# 2_BLE-T2_matrix.net
KiCad netlist of a schematic drawn in Altium Designer
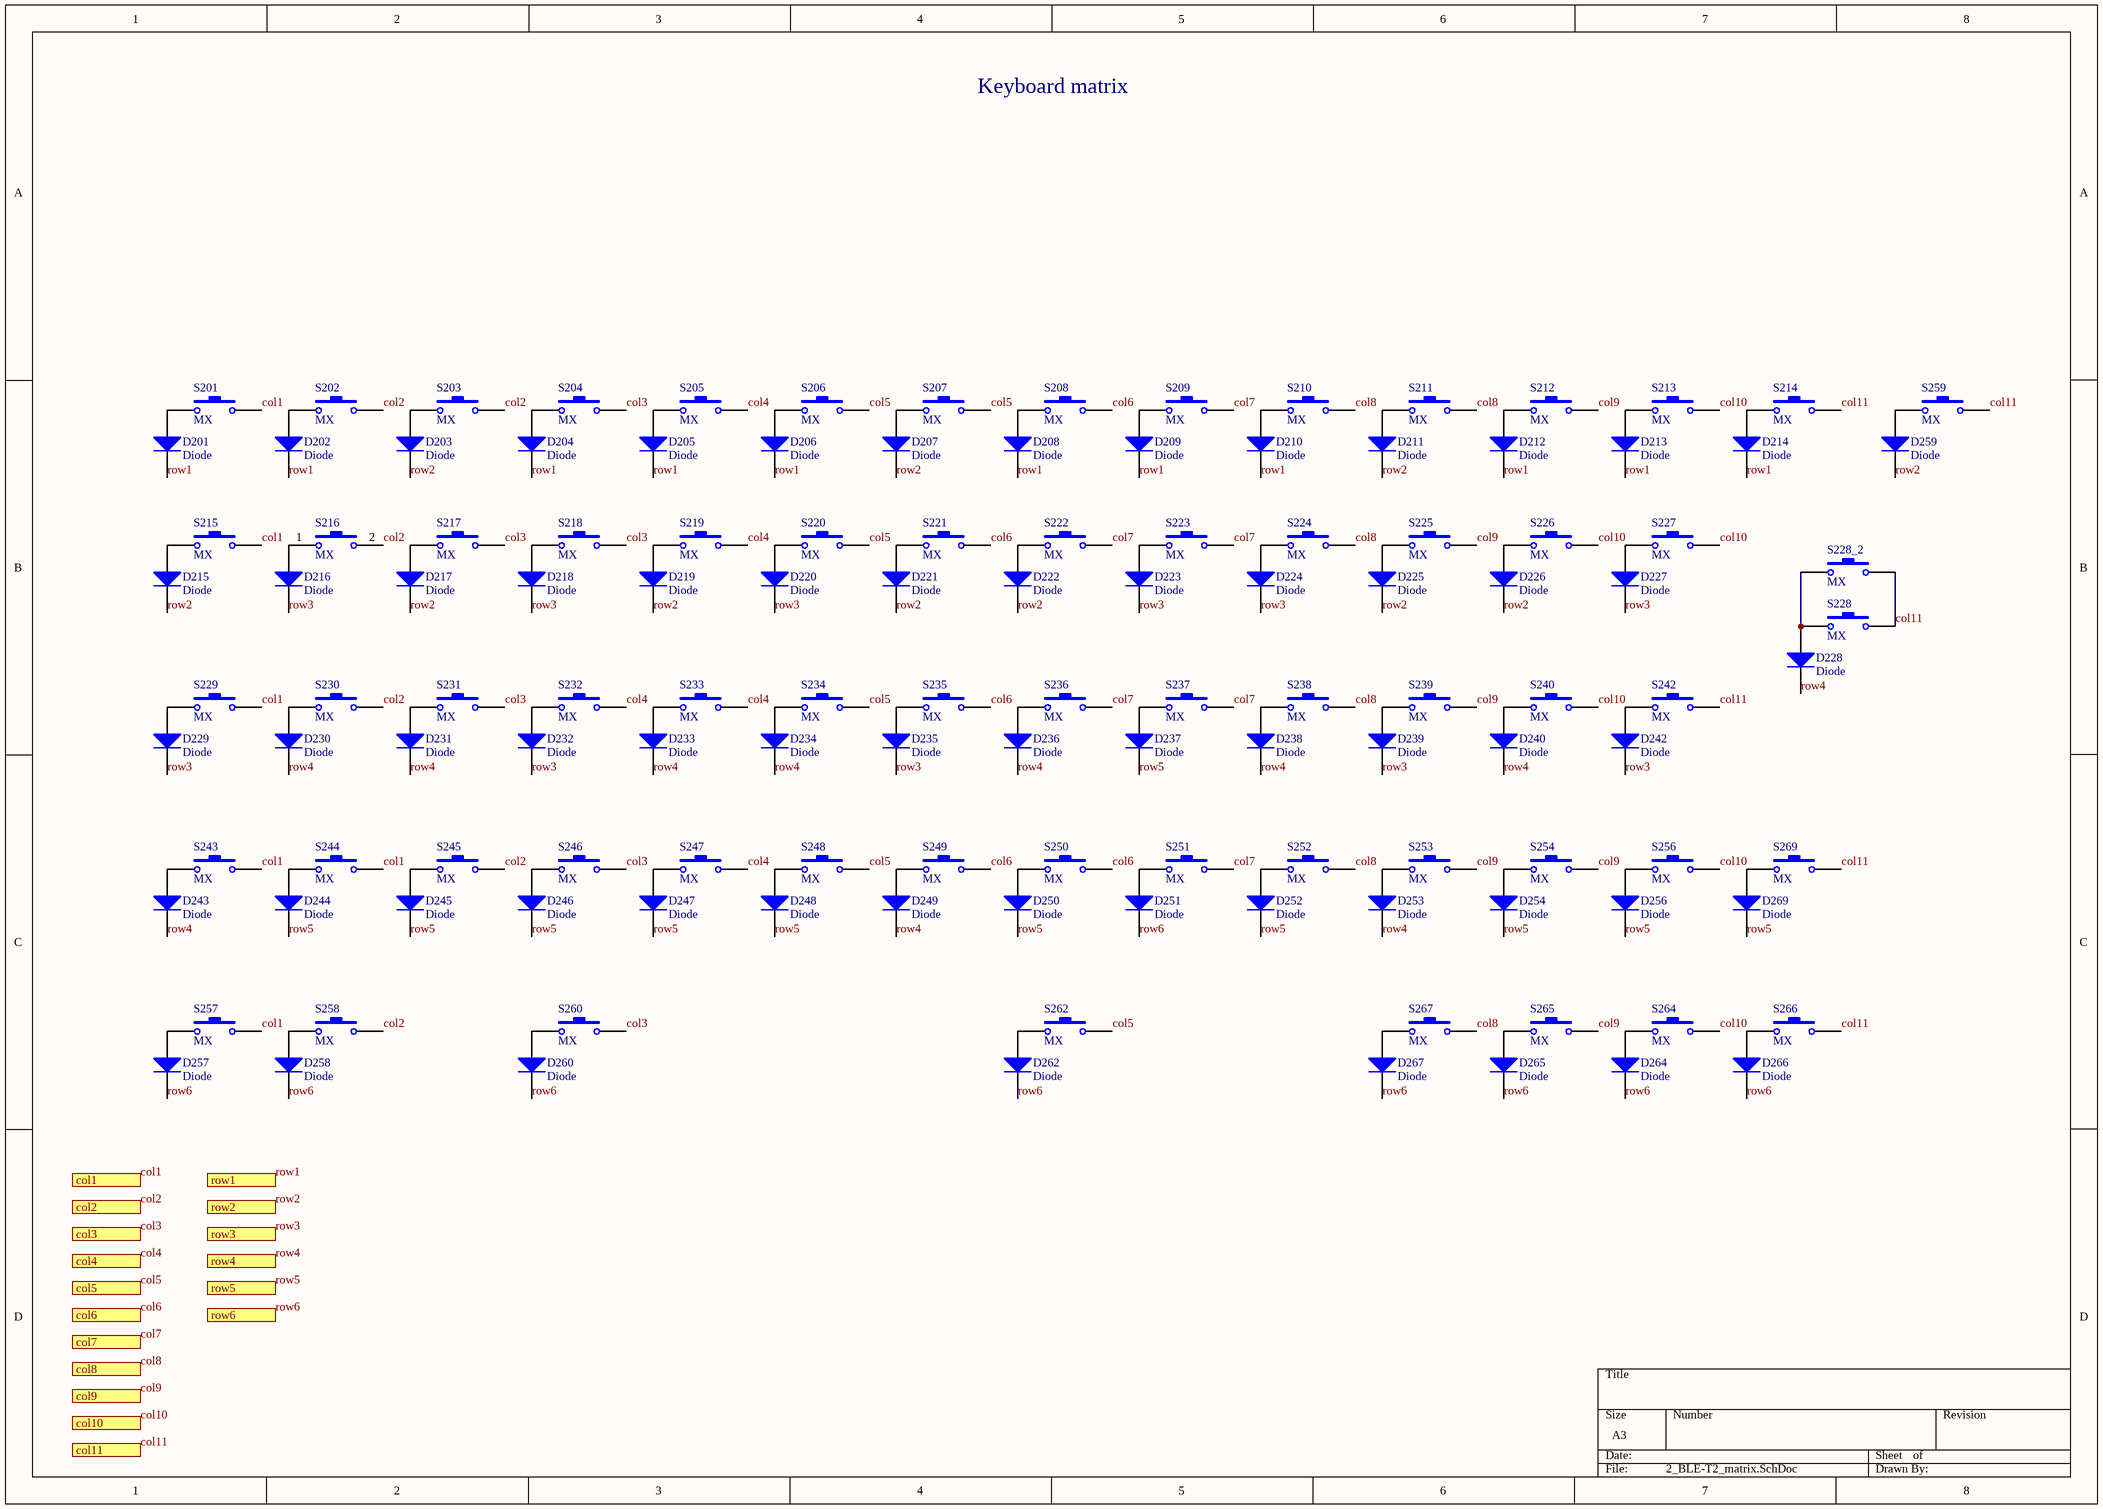
[diagram p0: 2_BLE-T2_matrix.SchDoc]

(export (version "E")
  (design (tool "Eeschema 10.0.6"))
  (components
    (comp (ref "D201")
      (value "Diode")
      (footprint "SOD-123")
      (description "Default Diode")
      (fields (field (name "LCSC PART #") "C81598") (field (name "MRF.PART") "1N4148W"))
      (libsource (lib "Miscellaneous Devices") (part "Diode"))
    )
    (comp (ref "D202")
      (value "Diode")
      (footprint "SOD-123")
      (description "Default Diode")
      (fields (field (name "LCSC PART #") "C81598") (field (name "MRF.PART") "1N4148W"))
      (libsource (lib "Miscellaneous Devices") (part "Diode"))
    )
    (comp (ref "D203")
      (value "Diode")
      (footprint "SOD-123")
      (description "Default Diode")
      (fields (field (name "LCSC PART #") "C81598") (field (name "MRF.PART") "1N4148W"))
      (libsource (lib "Miscellaneous Devices") (part "Diode"))
    )
    (comp (ref "D204")
      (value "Diode")
      (footprint "SOD-123")
      (description "Default Diode")
      (fields (field (name "LCSC PART #") "C81598") (field (name "MRF.PART") "1N4148W"))
      (libsource (lib "Miscellaneous Devices") (part "Diode"))
    )
    (comp (ref "D205")
      (value "Diode")
      (footprint "SOD-123")
      (description "Default Diode")
      (fields (field (name "LCSC PART #") "C81598") (field (name "MRF.PART") "1N4148W"))
      (libsource (lib "Miscellaneous Devices") (part "Diode"))
    )
    (comp (ref "D206")
      (value "Diode")
      (footprint "SOD-123")
      (description "Default Diode")
      (fields (field (name "LCSC PART #") "C81598") (field (name "MRF.PART") "1N4148W"))
      (libsource (lib "Miscellaneous Devices") (part "Diode"))
    )
    (comp (ref "D207")
      (value "Diode")
      (footprint "SOD-123")
      (description "Default Diode")
      (fields (field (name "LCSC PART #") "C81598") (field (name "MRF.PART") "1N4148W"))
      (libsource (lib "Miscellaneous Devices") (part "Diode"))
    )
    (comp (ref "D208")
      (value "Diode")
      (footprint "SOD-123")
      (description "Default Diode")
      (fields (field (name "LCSC PART #") "C81598") (field (name "MRF.PART") "1N4148W"))
      (libsource (lib "Miscellaneous Devices") (part "Diode"))
    )
    (comp (ref "D209")
      (value "Diode")
      (footprint "SOD-123")
      (description "Default Diode")
      (fields (field (name "LCSC PART #") "C81598") (field (name "MRF.PART") "1N4148W"))
      (libsource (lib "Miscellaneous Devices") (part "Diode"))
    )
    (comp (ref "D210")
      (value "Diode")
      (footprint "SOD-123")
      (description "Default Diode")
      (fields (field (name "LCSC PART #") "C81598") (field (name "MRF.PART") "1N4148W"))
      (libsource (lib "Miscellaneous Devices") (part "Diode"))
    )
    (comp (ref "D211")
      (value "Diode")
      (footprint "SOD-123")
      (description "Default Diode")
      (fields (field (name "LCSC PART #") "C81598") (field (name "MRF.PART") "1N4148W"))
      (libsource (lib "Miscellaneous Devices") (part "Diode"))
    )
    (comp (ref "D212")
      (value "Diode")
      (footprint "SOD-123")
      (description "Default Diode")
      (fields (field (name "LCSC PART #") "C81598") (field (name "MRF.PART") "1N4148W"))
      (libsource (lib "Miscellaneous Devices") (part "Diode"))
    )
    (comp (ref "D213")
      (value "Diode")
      (footprint "SOD-123")
      (description "Default Diode")
      (fields (field (name "LCSC PART #") "C81598") (field (name "MRF.PART") "1N4148W"))
      (libsource (lib "Miscellaneous Devices") (part "Diode"))
    )
    (comp (ref "D214")
      (value "Diode")
      (footprint "SOD-123")
      (description "Default Diode")
      (fields (field (name "LCSC PART #") "C81598") (field (name "MRF.PART") "1N4148W"))
      (libsource (lib "Miscellaneous Devices") (part "Diode"))
    )
    (comp (ref "D215")
      (value "Diode")
      (footprint "SOD-123")
      (description "Default Diode")
      (fields (field (name "LCSC PART #") "C81598") (field (name "MRF.PART") "1N4148W"))
      (libsource (lib "Miscellaneous Devices") (part "Diode"))
    )
    (comp (ref "D216")
      (value "Diode")
      (footprint "SOD-123")
      (description "Default Diode")
      (fields (field (name "LCSC PART #") "C81598") (field (name "MRF.PART") "1N4148W"))
      (libsource (lib "Miscellaneous Devices") (part "Diode"))
    )
    (comp (ref "D217")
      (value "Diode")
      (footprint "SOD-123")
      (description "Default Diode")
      (fields (field (name "LCSC PART #") "C81598") (field (name "MRF.PART") "1N4148W"))
      (libsource (lib "Miscellaneous Devices") (part "Diode"))
    )
    (comp (ref "D218")
      (value "Diode")
      (footprint "SOD-123")
      (description "Default Diode")
      (fields (field (name "LCSC PART #") "C81598") (field (name "MRF.PART") "1N4148W"))
      (libsource (lib "Miscellaneous Devices") (part "Diode"))
    )
    (comp (ref "D219")
      (value "Diode")
      (footprint "SOD-123")
      (description "Default Diode")
      (fields (field (name "LCSC PART #") "C81598") (field (name "MRF.PART") "1N4148W"))
      (libsource (lib "Miscellaneous Devices") (part "Diode"))
    )
    (comp (ref "D220")
      (value "Diode")
      (footprint "SOD-123")
      (description "Default Diode")
      (fields (field (name "LCSC PART #") "C81598") (field (name "MRF.PART") "1N4148W"))
      (libsource (lib "Miscellaneous Devices") (part "Diode"))
    )
    (comp (ref "D221")
      (value "Diode")
      (footprint "SOD-123")
      (description "Default Diode")
      (fields (field (name "LCSC PART #") "C81598") (field (name "MRF.PART") "1N4148W"))
      (libsource (lib "Miscellaneous Devices") (part "Diode"))
    )
    (comp (ref "D222")
      (value "Diode")
      (footprint "SOD-123")
      (description "Default Diode")
      (fields (field (name "LCSC PART #") "C81598") (field (name "MRF.PART") "1N4148W"))
      (libsource (lib "Miscellaneous Devices") (part "Diode"))
    )
    (comp (ref "D223")
      (value "Diode")
      (footprint "SOD-123")
      (description "Default Diode")
      (fields (field (name "LCSC PART #") "C81598") (field (name "MRF.PART") "1N4148W"))
      (libsource (lib "Miscellaneous Devices") (part "Diode"))
    )
    (comp (ref "D224")
      (value "Diode")
      (footprint "SOD-123")
      (description "Default Diode")
      (fields (field (name "LCSC PART #") "C81598") (field (name "MRF.PART") "1N4148W"))
      (libsource (lib "Miscellaneous Devices") (part "Diode"))
    )
    (comp (ref "D225")
      (value "Diode")
      (footprint "SOD-123")
      (description "Default Diode")
      (fields (field (name "LCSC PART #") "C81598") (field (name "MRF.PART") "1N4148W"))
      (libsource (lib "Miscellaneous Devices") (part "Diode"))
    )
    (comp (ref "D226")
      (value "Diode")
      (footprint "SOD-123")
      (description "Default Diode")
      (fields (field (name "LCSC PART #") "C81598") (field (name "MRF.PART") "1N4148W"))
      (libsource (lib "Miscellaneous Devices") (part "Diode"))
    )
    (comp (ref "D227")
      (value "Diode")
      (footprint "SOD-123")
      (description "Default Diode")
      (fields (field (name "LCSC PART #") "C81598") (field (name "MRF.PART") "1N4148W"))
      (libsource (lib "Miscellaneous Devices") (part "Diode"))
    )
    (comp (ref "D228")
      (value "Diode")
      (footprint "SOD-123")
      (description "Default Diode")
      (fields (field (name "LCSC PART #") "C81598") (field (name "MRF.PART") "1N4148W"))
      (libsource (lib "Miscellaneous Devices") (part "Diode"))
    )
    (comp (ref "D229")
      (value "Diode")
      (footprint "SOD-123")
      (description "Default Diode")
      (fields (field (name "LCSC PART #") "C81598") (field (name "MRF.PART") "1N4148W"))
      (libsource (lib "Miscellaneous Devices") (part "Diode"))
    )
    (comp (ref "D230")
      (value "Diode")
      (footprint "SOD-123")
      (description "Default Diode")
      (fields (field (name "LCSC PART #") "C81598") (field (name "MRF.PART") "1N4148W"))
      (libsource (lib "Miscellaneous Devices") (part "Diode"))
    )
    (comp (ref "D231")
      (value "Diode")
      (footprint "SOD-123")
      (description "Default Diode")
      (fields (field (name "LCSC PART #") "C81598") (field (name "MRF.PART") "1N4148W"))
      (libsource (lib "Miscellaneous Devices") (part "Diode"))
    )
    (comp (ref "D232")
      (value "Diode")
      (footprint "SOD-123")
      (description "Default Diode")
      (fields (field (name "LCSC PART #") "C81598") (field (name "MRF.PART") "1N4148W"))
      (libsource (lib "Miscellaneous Devices") (part "Diode"))
    )
    (comp (ref "D233")
      (value "Diode")
      (footprint "SOD-123")
      (description "Default Diode")
      (fields (field (name "LCSC PART #") "C81598") (field (name "MRF.PART") "1N4148W"))
      (libsource (lib "Miscellaneous Devices") (part "Diode"))
    )
    (comp (ref "D234")
      (value "Diode")
      (footprint "SOD-123")
      (description "Default Diode")
      (fields (field (name "LCSC PART #") "C81598") (field (name "MRF.PART") "1N4148W"))
      (libsource (lib "Miscellaneous Devices") (part "Diode"))
    )
    (comp (ref "D235")
      (value "Diode")
      (footprint "SOD-123")
      (description "Default Diode")
      (fields (field (name "LCSC PART #") "C81598") (field (name "MRF.PART") "1N4148W"))
      (libsource (lib "Miscellaneous Devices") (part "Diode"))
    )
    (comp (ref "D236")
      (value "Diode")
      (footprint "SOD-123")
      (description "Default Diode")
      (fields (field (name "LCSC PART #") "C81598") (field (name "MRF.PART") "1N4148W"))
      (libsource (lib "Miscellaneous Devices") (part "Diode"))
    )
    (comp (ref "D237")
      (value "Diode")
      (footprint "SOD-123")
      (description "Default Diode")
      (fields (field (name "LCSC PART #") "C81598") (field (name "MRF.PART") "1N4148W"))
      (libsource (lib "Miscellaneous Devices") (part "Diode"))
    )
    (comp (ref "D238")
      (value "Diode")
      (footprint "SOD-123")
      (description "Default Diode")
      (fields (field (name "LCSC PART #") "C81598") (field (name "MRF.PART") "1N4148W"))
      (libsource (lib "Miscellaneous Devices") (part "Diode"))
    )
    (comp (ref "D239")
      (value "Diode")
      (footprint "SOD-123")
      (description "Default Diode")
      (fields (field (name "LCSC PART #") "C81598") (field (name "MRF.PART") "1N4148W"))
      (libsource (lib "Miscellaneous Devices") (part "Diode"))
    )
    (comp (ref "D240")
      (value "Diode")
      (footprint "SOD-123")
      (description "Default Diode")
      (fields (field (name "LCSC PART #") "C81598") (field (name "MRF.PART") "1N4148W"))
      (libsource (lib "Miscellaneous Devices") (part "Diode"))
    )
    (comp (ref "D242")
      (value "Diode")
      (footprint "SOD-123")
      (description "Default Diode")
      (fields (field (name "LCSC PART #") "C81598") (field (name "MRF.PART") "1N4148W"))
      (libsource (lib "Miscellaneous Devices") (part "Diode"))
    )
    (comp (ref "D243")
      (value "Diode")
      (footprint "SOD-123")
      (description "Default Diode")
      (fields (field (name "LCSC PART #") "C81598") (field (name "MRF.PART") "1N4148W"))
      (libsource (lib "Miscellaneous Devices") (part "Diode"))
    )
    (comp (ref "D244")
      (value "Diode")
      (footprint "SOD-123")
      (description "Default Diode")
      (fields (field (name "LCSC PART #") "C81598") (field (name "MRF.PART") "1N4148W"))
      (libsource (lib "Miscellaneous Devices") (part "Diode"))
    )
    (comp (ref "D245")
      (value "Diode")
      (footprint "SOD-123")
      (description "Default Diode")
      (fields (field (name "LCSC PART #") "C81598") (field (name "MRF.PART") "1N4148W"))
      (libsource (lib "Miscellaneous Devices") (part "Diode"))
    )
    (comp (ref "D246")
      (value "Diode")
      (footprint "SOD-123")
      (description "Default Diode")
      (fields (field (name "LCSC PART #") "C81598") (field (name "MRF.PART") "1N4148W"))
      (libsource (lib "Miscellaneous Devices") (part "Diode"))
    )
    (comp (ref "D247")
      (value "Diode")
      (footprint "SOD-123")
      (description "Default Diode")
      (fields (field (name "LCSC PART #") "C81598") (field (name "MRF.PART") "1N4148W"))
      (libsource (lib "Miscellaneous Devices") (part "Diode"))
    )
    (comp (ref "D248")
      (value "Diode")
      (footprint "SOD-123")
      (description "Default Diode")
      (fields (field (name "LCSC PART #") "C81598") (field (name "MRF.PART") "1N4148W"))
      (libsource (lib "Miscellaneous Devices") (part "Diode"))
    )
    (comp (ref "D249")
      (value "Diode")
      (footprint "SOD-123")
      (description "Default Diode")
      (fields (field (name "LCSC PART #") "C81598") (field (name "MRF.PART") "1N4148W"))
      (libsource (lib "Miscellaneous Devices") (part "Diode"))
    )
    (comp (ref "D250")
      (value "Diode")
      (footprint "SOD-123")
      (description "Default Diode")
      (fields (field (name "LCSC PART #") "C81598") (field (name "MRF.PART") "1N4148W"))
      (libsource (lib "Miscellaneous Devices") (part "Diode"))
    )
    (comp (ref "D251")
      (value "Diode")
      (footprint "SOD-123")
      (description "Default Diode")
      (fields (field (name "LCSC PART #") "C81598") (field (name "MRF.PART") "1N4148W"))
      (libsource (lib "Miscellaneous Devices") (part "Diode"))
    )
    (comp (ref "D252")
      (value "Diode")
      (footprint "SOD-123")
      (description "Default Diode")
      (fields (field (name "LCSC PART #") "C81598") (field (name "MRF.PART") "1N4148W"))
      (libsource (lib "Miscellaneous Devices") (part "Diode"))
    )
    (comp (ref "D253")
      (value "Diode")
      (footprint "SOD-123")
      (description "Default Diode")
      (fields (field (name "LCSC PART #") "C81598") (field (name "MRF.PART") "1N4148W"))
      (libsource (lib "Miscellaneous Devices") (part "Diode"))
    )
    (comp (ref "D254")
      (value "Diode")
      (footprint "SOD-123")
      (description "Default Diode")
      (fields (field (name "LCSC PART #") "C81598") (field (name "MRF.PART") "1N4148W"))
      (libsource (lib "Miscellaneous Devices") (part "Diode"))
    )
    (comp (ref "D256")
      (value "Diode")
      (footprint "SOD-123")
      (description "Default Diode")
      (fields (field (name "LCSC PART #") "C81598") (field (name "MRF.PART") "1N4148W"))
      (libsource (lib "Miscellaneous Devices") (part "Diode"))
    )
    (comp (ref "D257")
      (value "Diode")
      (footprint "SOD-123")
      (description "Default Diode")
      (fields (field (name "LCSC PART #") "C81598") (field (name "MRF.PART") "1N4148W"))
      (libsource (lib "Miscellaneous Devices") (part "Diode"))
    )
    (comp (ref "D258")
      (value "Diode")
      (footprint "SOD-123")
      (description "Default Diode")
      (fields (field (name "LCSC PART #") "C81598") (field (name "MRF.PART") "1N4148W"))
      (libsource (lib "Miscellaneous Devices") (part "Diode"))
    )
    (comp (ref "D259")
      (value "Diode")
      (footprint "SOD-123")
      (description "Default Diode")
      (fields (field (name "LCSC PART #") "C81598") (field (name "MRF.PART") "1N4148W"))
      (libsource (lib "Miscellaneous Devices") (part "Diode"))
    )
    (comp (ref "D260")
      (value "Diode")
      (footprint "SOD-123")
      (description "Default Diode")
      (fields (field (name "LCSC PART #") "C81598") (field (name "MRF.PART") "1N4148W"))
      (libsource (lib "Miscellaneous Devices") (part "Diode"))
    )
    (comp (ref "D262")
      (value "Diode")
      (footprint "SOD-123")
      (description "Default Diode")
      (fields (field (name "LCSC PART #") "C81598") (field (name "MRF.PART") "1N4148W"))
      (libsource (lib "Miscellaneous Devices") (part "Diode"))
    )
    (comp (ref "D264")
      (value "Diode")
      (footprint "SOD-123")
      (description "Default Diode")
      (fields (field (name "LCSC PART #") "C81598") (field (name "MRF.PART") "1N4148W"))
      (libsource (lib "Miscellaneous Devices") (part "Diode"))
    )
    (comp (ref "D265")
      (value "Diode")
      (footprint "SOD-123")
      (description "Default Diode")
      (fields (field (name "LCSC PART #") "C81598") (field (name "MRF.PART") "1N4148W"))
      (libsource (lib "Miscellaneous Devices") (part "Diode"))
    )
    (comp (ref "D266")
      (value "Diode")
      (footprint "SOD-123")
      (description "Default Diode")
      (fields (field (name "LCSC PART #") "C81598") (field (name "MRF.PART") "1N4148W"))
      (libsource (lib "Miscellaneous Devices") (part "Diode"))
    )
    (comp (ref "D267")
      (value "Diode")
      (footprint "SOD-123")
      (description "Default Diode")
      (fields (field (name "LCSC PART #") "C81598") (field (name "MRF.PART") "1N4148W"))
      (libsource (lib "Miscellaneous Devices") (part "Diode"))
    )
    (comp (ref "D269")
      (value "Diode")
      (footprint "SOD-123")
      (description "Default Diode")
      (fields (field (name "LCSC PART #") "C81598") (field (name "MRF.PART") "1N4148W"))
      (libsource (lib "Miscellaneous Devices") (part "Diode"))
    )
    (comp (ref "S201")
      (value "MX")
      (footprint "MX-switch - switched pol")
      (description "Switch")
      (libsource (lib "Miscellaneous Devices") (part "SW-PB"))
    )
    (comp (ref "S202")
      (value "MX")
      (footprint "MX-switch - switched pol - connector")
      (description "Switch")
      (libsource (lib "Miscellaneous Devices") (part "SW-PB"))
    )
    (comp (ref "S203")
      (value "MX")
      (footprint "MX-switch - switched pol")
      (description "Switch")
      (libsource (lib "Miscellaneous Devices") (part "SW-PB"))
    )
    (comp (ref "S204")
      (value "MX")
      (footprint "MX-switch")
      (description "Switch")
      (libsource (lib "Miscellaneous Devices") (part "SW-PB"))
    )
    (comp (ref "S205")
      (value "MX")
      (footprint "MX-switch - switched pol")
      (description "Switch")
      (libsource (lib "Miscellaneous Devices") (part "SW-PB"))
    )
    (comp (ref "S206")
      (value "MX")
      (footprint "MX-switch")
      (description "Switch")
      (libsource (lib "Miscellaneous Devices") (part "SW-PB"))
    )
    (comp (ref "S207")
      (value "MX")
      (footprint "MX-switch")
      (description "Switch")
      (libsource (lib "Miscellaneous Devices") (part "SW-PB"))
    )
    (comp (ref "S208")
      (value "MX")
      (footprint "MX-switch")
      (description "Switch")
      (libsource (lib "Miscellaneous Devices") (part "SW-PB"))
    )
    (comp (ref "S209")
      (value "MX")
      (footprint "MX-switch")
      (description "Switch")
      (libsource (lib "Miscellaneous Devices") (part "SW-PB"))
    )
    (comp (ref "S210")
      (value "MX")
      (footprint "MX-switch")
      (description "Switch")
      (libsource (lib "Miscellaneous Devices") (part "SW-PB"))
    )
    (comp (ref "S211")
      (value "MX")
      (footprint "MX-switch - switched pol")
      (description "Switch")
      (libsource (lib "Miscellaneous Devices") (part "SW-PB"))
    )
    (comp (ref "S212")
      (value "MX")
      (footprint "MX-switch")
      (description "Switch")
      (libsource (lib "Miscellaneous Devices") (part "SW-PB"))
    )
    (comp (ref "S213")
      (value "MX")
      (footprint "MX-switch")
      (description "Switch")
      (libsource (lib "Miscellaneous Devices") (part "SW-PB"))
    )
    (comp (ref "S214")
      (value "MX")
      (footprint "MX-switch")
      (description "Switch")
      (libsource (lib "Miscellaneous Devices") (part "SW-PB"))
    )
    (comp (ref "S215")
      (value "MX")
      (footprint "MX-switch - 1.5U")
      (description "TAB")
      (libsource (lib "Miscellaneous Devices") (part "SW-PB"))
    )
    (comp (ref "S216")
      (value "MX")
      (footprint "MX-switch - switched pol")
      (description "Switch")
      (libsource (lib "") (part "SW-PB_1"))
    )
    (comp (ref "S217")
      (value "MX")
      (footprint "MX-switch - switched pol")
      (description "Switch")
      (libsource (lib "Miscellaneous Devices") (part "SW-PB"))
    )
    (comp (ref "S218")
      (value "MX")
      (footprint "MX-switch - switched pol")
      (description "Switch")
      (libsource (lib "Miscellaneous Devices") (part "SW-PB"))
    )
    (comp (ref "S219")
      (value "MX")
      (footprint "MX-switch - switched pol")
      (description "Switch")
      (libsource (lib "Miscellaneous Devices") (part "SW-PB"))
    )
    (comp (ref "S220")
      (value "MX")
      (footprint "MX-switch")
      (description "Switch")
      (libsource (lib "Miscellaneous Devices") (part "SW-PB"))
    )
    (comp (ref "S221")
      (value "MX")
      (footprint "MX-switch - switched pol")
      (description "Switch")
      (libsource (lib "Miscellaneous Devices") (part "SW-PB"))
    )
    (comp (ref "S222")
      (value "MX")
      (footprint "MX-switch")
      (description "Switch")
      (libsource (lib "Miscellaneous Devices") (part "SW-PB"))
    )
    (comp (ref "S223")
      (value "MX")
      (footprint "MX-switch - switched pol")
      (description "Switch")
      (libsource (lib "Miscellaneous Devices") (part "SW-PB"))
    )
    (comp (ref "S224")
      (value "MX")
      (footprint "MX-switch - switched pol")
      (description "Switch")
      (libsource (lib "Miscellaneous Devices") (part "SW-PB"))
    )
    (comp (ref "S225")
      (value "MX")
      (footprint "MX-switch - switched pol")
      (description "Switch")
      (libsource (lib "Miscellaneous Devices") (part "SW-PB"))
    )
    (comp (ref "S226")
      (value "MX")
      (footprint "MX-switch - switched pol")
      (description "Switch")
      (libsource (lib "Miscellaneous Devices") (part "SW-PB"))
    )
    (comp (ref "S227")
      (value "MX")
      (footprint "MX-switch")
      (description "Switch")
      (libsource (lib "Miscellaneous Devices") (part "SW-PB"))
    )
    (comp (ref "S228")
      (value "MX")
      (footprint "MX-switch - 1.5U")
      (description "Switch")
      (libsource (lib "Miscellaneous Devices") (part "SW-PB"))
    )
    (comp (ref "S228_2")
      (value "MX")
      (footprint "MX-switch")
      (description "Switch")
      (libsource (lib "Miscellaneous Devices") (part "SW-PB"))
    )
    (comp (ref "S229")
      (value "MX")
      (footprint "MX-switch - CAPS")
      (description "Switch")
      (libsource (lib "Miscellaneous Devices") (part "SW-PB"))
    )
    (comp (ref "S230")
      (value "MX")
      (footprint "MX-switch - switched pol")
      (description "Switch")
      (libsource (lib "Miscellaneous Devices") (part "SW-PB"))
    )
    (comp (ref "S231")
      (value "MX")
      (footprint "MX-switch - switched pol")
      (description "Switch")
      (libsource (lib "Miscellaneous Devices") (part "SW-PB"))
    )
    (comp (ref "S232")
      (value "MX")
      (footprint "MX-switch - switched pol")
      (description "Switch")
      (libsource (lib "Miscellaneous Devices") (part "SW-PB"))
    )
    (comp (ref "S233")
      (value "MX")
      (footprint "MX-switch - switched pol")
      (description "Switch")
      (libsource (lib "Miscellaneous Devices") (part "SW-PB"))
    )
    (comp (ref "S234")
      (value "MX")
      (footprint "MX-switch")
      (description "Switch")
      (libsource (lib "Miscellaneous Devices") (part "SW-PB"))
    )
    (comp (ref "S235")
      (value "MX")
      (footprint "MX-switch - switched pol")
      (description "Switch")
      (libsource (lib "Miscellaneous Devices") (part "SW-PB"))
    )
    (comp (ref "S236")
      (value "MX")
      (footprint "MX-switch - switched pol")
      (description "Switch")
      (libsource (lib "Miscellaneous Devices") (part "SW-PB"))
    )
    (comp (ref "S237")
      (value "MX")
      (footprint "MX-switch - switched pol")
      (description "Switch")
      (libsource (lib "Miscellaneous Devices") (part "SW-PB"))
    )
    (comp (ref "S238")
      (value "MX")
      (footprint "MX-switch - switched pol")
      (description "Switch")
      (libsource (lib "Miscellaneous Devices") (part "SW-PB"))
    )
    (comp (ref "S239")
      (value "MX")
      (footprint "MX-switch - switched pol")
      (description "Switch")
      (libsource (lib "Miscellaneous Devices") (part "SW-PB"))
    )
    (comp (ref "S240")
      (value "MX")
      (footprint "MX-switch - switched pol")
      (description "Switch")
      (libsource (lib "Miscellaneous Devices") (part "SW-PB"))
    )
    (comp (ref "S242")
      (value "MX")
      (footprint "MX-switch - Enter")
      (description "Switch")
      (libsource (lib "Miscellaneous Devices") (part "SW-PB"))
    )
    (comp (ref "S243")
      (value "MX")
      (footprint "MX-switch - Left shift")
      (description "Switch")
      (libsource (lib "Miscellaneous Devices") (part "SW-PB"))
    )
    (comp (ref "S244")
      (value "MX")
      (footprint "MX-switch - switched pol")
      (description "Switch")
      (libsource (lib "Miscellaneous Devices") (part "SW-PB"))
    )
    (comp (ref "S245")
      (value "MX")
      (footprint "MX-switch - switched pol")
      (description "Switch")
      (libsource (lib "Miscellaneous Devices") (part "SW-PB"))
    )
    (comp (ref "S246")
      (value "MX")
      (footprint "MX-switch - switched pol")
      (description "Switch")
      (libsource (lib "Miscellaneous Devices") (part "SW-PB"))
    )
    (comp (ref "S247")
      (value "MX")
      (footprint "MX-switch - switched pol")
      (description "Switch")
      (libsource (lib "Miscellaneous Devices") (part "SW-PB"))
    )
    (comp (ref "S248")
      (value "MX")
      (footprint "MX-switch - switched pol")
      (description "Switch")
      (libsource (lib "Miscellaneous Devices") (part "SW-PB"))
    )
    (comp (ref "S249")
      (value "MX")
      (footprint "MX-switch - switched pol")
      (description "Switch")
      (libsource (lib "Miscellaneous Devices") (part "SW-PB"))
    )
    (comp (ref "S250")
      (value "MX")
      (footprint "MX-switch - switched pol")
      (description "Switch")
      (libsource (lib "Miscellaneous Devices") (part "SW-PB"))
    )
    (comp (ref "S251")
      (value "MX")
      (footprint "MX-switch - switched pol")
      (description "Switch")
      (libsource (lib "Miscellaneous Devices") (part "SW-PB"))
    )
    (comp (ref "S252")
      (value "MX")
      (footprint "MX-switch - switched pol")
      (description "Switch")
      (libsource (lib "Miscellaneous Devices") (part "SW-PB"))
    )
    (comp (ref "S253")
      (value "MX")
      (footprint "MX-switch - switched pol")
      (description "Switch")
      (libsource (lib "Miscellaneous Devices") (part "SW-PB"))
    )
    (comp (ref "S254")
      (value "MX")
      (footprint "MX-switch - switched pol")
      (description "Switch")
      (libsource (lib "Miscellaneous Devices") (part "SW-PB"))
    )
    (comp (ref "S256")
      (value "MX")
      (footprint "MX-switch - right shift")
      (description "Switch")
      (libsource (lib "Miscellaneous Devices") (part "SW-PB"))
    )
    (comp (ref "S257")
      (value "MX")
      (footprint "MX-switch - 1.5u MOD-L")
      (description "Switch")
      (libsource (lib "Miscellaneous Devices") (part "SW-PB"))
    )
    (comp (ref "S258")
      (value "MX")
      (footprint "MX-switch - 1u MOD-L")
      (description "Switch")
      (libsource (lib "Miscellaneous Devices") (part "SW-PB"))
    )
    (comp (ref "S259")
      (value "MX")
      (footprint "MX-switch - backspace")
      (description "Switch")
      (libsource (lib "Miscellaneous Devices") (part "SW-PB"))
    )
    (comp (ref "S260")
      (value "MX")
      (footprint "MX-switch - 1.5u MOD-L")
      (description "Switch")
      (libsource (lib "Miscellaneous Devices") (part "SW-PB"))
    )
    (comp (ref "S262")
      (value "MX")
      (footprint "MX-SWITCH - SPACE_V2")
      (description "Switch")
      (libsource (lib "Miscellaneous Devices") (part "SW-PB"))
    )
    (comp (ref "S264")
      (value "MX")
      (footprint "MX-switch - 1u MOD-R")
      (description "Switch")
      (libsource (lib "Miscellaneous Devices") (part "SW-PB"))
    )
    (comp (ref "S265")
      (value "MX")
      (footprint "MX-switch - 1.5u MOD-R")
      (description "Switch")
      (libsource (lib "Miscellaneous Devices") (part "SW-PB"))
    )
    (comp (ref "S266")
      (value "MX")
      (footprint "MX-switch - 1.5u MOD-R")
      (description "Switch")
      (libsource (lib "Miscellaneous Devices") (part "SW-PB"))
    )
    (comp (ref "S267")
      (value "MX")
      (footprint "MX-switch - switched pol")
      (description "Switch")
      (libsource (lib "Miscellaneous Devices") (part "SW-PB"))
    )
    (comp (ref "S269")
      (value "MX")
      (footprint "MX-switch")
      (description "Switch")
      (libsource (lib "Miscellaneous Devices") (part "SW-PB"))
    )
  )
  (nets
    (net (code "1") (name "/col1") (class "Default")
      (node (ref "S201") (pin "2") (pinfunction "2_2") (pintype "passive"))
      (node (ref "S215") (pin "2") (pinfunction "2_2") (pintype "passive"))
      (node (ref "S229") (pin "2") (pinfunction "2_2") (pintype "passive"))
      (node (ref "S243") (pin "2") (pinfunction "2_2") (pintype "passive"))
      (node (ref "S244") (pin "2") (pinfunction "2_2") (pintype "passive"))
      (node (ref "S257") (pin "2") (pinfunction "2_2") (pintype "passive"))
    )
    (net (code "2") (name "/col2") (class "Default")
      (node (ref "S202") (pin "2") (pinfunction "2_2") (pintype "passive"))
      (node (ref "S203") (pin "2") (pinfunction "2_2") (pintype "passive"))
      (node (ref "S216") (pin "2") (pinfunction "2_2") (pintype "passive"))
      (node (ref "S230") (pin "2") (pinfunction "2_2") (pintype "passive"))
      (node (ref "S245") (pin "2") (pinfunction "2_2") (pintype "passive"))
      (node (ref "S258") (pin "1") (pinfunction "1_1") (pintype "passive"))
    )
    (net (code "3") (name "/col3") (class "Default")
      (node (ref "S204") (pin "2") (pinfunction "2_2") (pintype "passive"))
      (node (ref "S217") (pin "2") (pinfunction "2_2") (pintype "passive"))
      (node (ref "S218") (pin "2") (pinfunction "2_2") (pintype "passive"))
      (node (ref "S231") (pin "2") (pinfunction "2_2") (pintype "passive"))
      (node (ref "S246") (pin "2") (pinfunction "2_2") (pintype "passive"))
      (node (ref "S260") (pin "2") (pinfunction "2_2") (pintype "passive"))
    )
    (net (code "4") (name "/col4") (class "Default")
      (node (ref "S205") (pin "2") (pinfunction "2_2") (pintype "passive"))
      (node (ref "S219") (pin "2") (pinfunction "2_2") (pintype "passive"))
      (node (ref "S232") (pin "2") (pinfunction "2_2") (pintype "passive"))
      (node (ref "S233") (pin "2") (pinfunction "2_2") (pintype "passive"))
      (node (ref "S247") (pin "2") (pinfunction "2_2") (pintype "passive"))
    )
    (net (code "5") (name "/col5") (class "Default")
      (node (ref "S206") (pin "2") (pinfunction "2_2") (pintype "passive"))
      (node (ref "S207") (pin "2") (pinfunction "2_2") (pintype "passive"))
      (node (ref "S220") (pin "2") (pinfunction "2_2") (pintype "passive"))
      (node (ref "S234") (pin "2") (pinfunction "2_2") (pintype "passive"))
      (node (ref "S248") (pin "2") (pinfunction "2_2") (pintype "passive"))
      (node (ref "S262") (pin "2") (pinfunction "2_2") (pintype "passive"))
    )
    (net (code "6") (name "/col6") (class "Default")
      (node (ref "S208") (pin "2") (pinfunction "2_2") (pintype "passive"))
      (node (ref "S221") (pin "2") (pinfunction "2_2") (pintype "passive"))
      (node (ref "S235") (pin "2") (pinfunction "2_2") (pintype "passive"))
      (node (ref "S249") (pin "2") (pinfunction "2_2") (pintype "passive"))
      (node (ref "S250") (pin "2") (pinfunction "2_2") (pintype "passive"))
    )
    (net (code "7") (name "/col7") (class "Default")
      (node (ref "S209") (pin "2") (pinfunction "2_2") (pintype "passive"))
      (node (ref "S222") (pin "2") (pinfunction "2_2") (pintype "passive"))
      (node (ref "S223") (pin "2") (pinfunction "2_2") (pintype "passive"))
      (node (ref "S236") (pin "2") (pinfunction "2_2") (pintype "passive"))
      (node (ref "S237") (pin "2") (pinfunction "2_2") (pintype "passive"))
      (node (ref "S251") (pin "2") (pinfunction "2_2") (pintype "passive"))
    )
    (net (code "8") (name "/col8") (class "Default")
      (node (ref "S210") (pin "2") (pinfunction "2_2") (pintype "passive"))
      (node (ref "S211") (pin "2") (pinfunction "2_2") (pintype "passive"))
      (node (ref "S224") (pin "2") (pinfunction "2_2") (pintype "passive"))
      (node (ref "S238") (pin "2") (pinfunction "2_2") (pintype "passive"))
      (node (ref "S252") (pin "2") (pinfunction "2_2") (pintype "passive"))
      (node (ref "S267") (pin "2") (pinfunction "2_2") (pintype "passive"))
    )
    (net (code "9") (name "/col9") (class "Default")
      (node (ref "S212") (pin "2") (pinfunction "2_2") (pintype "passive"))
      (node (ref "S225") (pin "2") (pinfunction "2_2") (pintype "passive"))
      (node (ref "S239") (pin "2") (pinfunction "2_2") (pintype "passive"))
      (node (ref "S253") (pin "2") (pinfunction "2_2") (pintype "passive"))
      (node (ref "S254") (pin "2") (pinfunction "2_2") (pintype "passive"))
      (node (ref "S265") (pin "1") (pinfunction "1_1") (pintype "passive"))
    )
    (net (code "10") (name "/col10") (class "Default")
      (node (ref "S213") (pin "2") (pinfunction "2_2") (pintype "passive"))
      (node (ref "S226") (pin "2") (pinfunction "2_2") (pintype "passive"))
      (node (ref "S227") (pin "2") (pinfunction "2_2") (pintype "passive"))
      (node (ref "S240") (pin "2") (pinfunction "2_2") (pintype "passive"))
      (node (ref "S256") (pin "2") (pinfunction "2_2") (pintype "passive"))
      (node (ref "S264") (pin "2") (pinfunction "2_2") (pintype "passive"))
    )
    (net (code "11") (name "/col11") (class "Default")
      (node (ref "S214") (pin "2") (pinfunction "2_2") (pintype "passive"))
      (node (ref "S228") (pin "2") (pinfunction "2_2") (pintype "passive"))
      (node (ref "S228_2") (pin "2") (pinfunction "2_2") (pintype "passive"))
      (node (ref "S242") (pin "2") (pinfunction "2_2") (pintype "passive"))
      (node (ref "S259") (pin "2") (pinfunction "2_2") (pintype "passive"))
      (node (ref "S266") (pin "1") (pinfunction "1_1") (pintype "passive"))
      (node (ref "S269") (pin "2") (pinfunction "2_2") (pintype "passive"))
    )
    (net (code "12") (name "/row1") (class "Default")
      (node (ref "D201") (pin "2") (pinfunction "K_2") (pintype "passive"))
      (node (ref "D202") (pin "2") (pinfunction "K_2") (pintype "passive"))
      (node (ref "D204") (pin "2") (pinfunction "K_2") (pintype "passive"))
      (node (ref "D205") (pin "2") (pinfunction "K_2") (pintype "passive"))
      (node (ref "D206") (pin "2") (pinfunction "K_2") (pintype "passive"))
      (node (ref "D208") (pin "2") (pinfunction "K_2") (pintype "passive"))
      (node (ref "D209") (pin "2") (pinfunction "K_2") (pintype "passive"))
      (node (ref "D210") (pin "2") (pinfunction "K_2") (pintype "passive"))
      (node (ref "D212") (pin "2") (pinfunction "K_2") (pintype "passive"))
      (node (ref "D213") (pin "2") (pinfunction "K_2") (pintype "passive"))
      (node (ref "D214") (pin "2") (pinfunction "K_2") (pintype "passive"))
    )
    (net (code "13") (name "/row2") (class "Default")
      (node (ref "D203") (pin "2") (pinfunction "K_2") (pintype "passive"))
      (node (ref "D207") (pin "2") (pinfunction "K_2") (pintype "passive"))
      (node (ref "D211") (pin "2") (pinfunction "K_2") (pintype "passive"))
      (node (ref "D215") (pin "2") (pinfunction "K_2") (pintype "passive"))
      (node (ref "D217") (pin "2") (pinfunction "K_2") (pintype "passive"))
      (node (ref "D219") (pin "2") (pinfunction "K_2") (pintype "passive"))
      (node (ref "D221") (pin "2") (pinfunction "K_2") (pintype "passive"))
      (node (ref "D222") (pin "2") (pinfunction "K_2") (pintype "passive"))
      (node (ref "D225") (pin "2") (pinfunction "K_2") (pintype "passive"))
      (node (ref "D226") (pin "2") (pinfunction "K_2") (pintype "passive"))
      (node (ref "D259") (pin "2") (pinfunction "K_2") (pintype "passive"))
    )
    (net (code "14") (name "/row3") (class "Default")
      (node (ref "D216") (pin "2") (pinfunction "K_2") (pintype "passive"))
      (node (ref "D218") (pin "2") (pinfunction "K_2") (pintype "passive"))
      (node (ref "D220") (pin "2") (pinfunction "K_2") (pintype "passive"))
      (node (ref "D223") (pin "2") (pinfunction "K_2") (pintype "passive"))
      (node (ref "D224") (pin "2") (pinfunction "K_2") (pintype "passive"))
      (node (ref "D227") (pin "2") (pinfunction "K_2") (pintype "passive"))
      (node (ref "D229") (pin "2") (pinfunction "K_2") (pintype "passive"))
      (node (ref "D232") (pin "2") (pinfunction "K_2") (pintype "passive"))
      (node (ref "D235") (pin "2") (pinfunction "K_2") (pintype "passive"))
      (node (ref "D239") (pin "2") (pinfunction "K_2") (pintype "passive"))
      (node (ref "D242") (pin "2") (pinfunction "K_2") (pintype "passive"))
    )
    (net (code "15") (name "/row4") (class "Default")
      (node (ref "D228") (pin "2") (pinfunction "K_2") (pintype "passive"))
      (node (ref "D230") (pin "2") (pinfunction "K_2") (pintype "passive"))
      (node (ref "D231") (pin "2") (pinfunction "K_2") (pintype "passive"))
      (node (ref "D233") (pin "2") (pinfunction "K_2") (pintype "passive"))
      (node (ref "D234") (pin "2") (pinfunction "K_2") (pintype "passive"))
      (node (ref "D236") (pin "2") (pinfunction "K_2") (pintype "passive"))
      (node (ref "D238") (pin "2") (pinfunction "K_2") (pintype "passive"))
      (node (ref "D240") (pin "2") (pinfunction "K_2") (pintype "passive"))
      (node (ref "D243") (pin "2") (pinfunction "K_2") (pintype "passive"))
      (node (ref "D249") (pin "2") (pinfunction "K_2") (pintype "passive"))
      (node (ref "D253") (pin "2") (pinfunction "K_2") (pintype "passive"))
    )
    (net (code "16") (name "/row5") (class "Default")
      (node (ref "D237") (pin "2") (pinfunction "K_2") (pintype "passive"))
      (node (ref "D244") (pin "2") (pinfunction "K_2") (pintype "passive"))
      (node (ref "D245") (pin "2") (pinfunction "K_2") (pintype "passive"))
      (node (ref "D246") (pin "2") (pinfunction "K_2") (pintype "passive"))
      (node (ref "D247") (pin "2") (pinfunction "K_2") (pintype "passive"))
      (node (ref "D248") (pin "2") (pinfunction "K_2") (pintype "passive"))
      (node (ref "D250") (pin "2") (pinfunction "K_2") (pintype "passive"))
      (node (ref "D252") (pin "2") (pinfunction "K_2") (pintype "passive"))
      (node (ref "D254") (pin "2") (pinfunction "K_2") (pintype "passive"))
      (node (ref "D256") (pin "2") (pinfunction "K_2") (pintype "passive"))
      (node (ref "D269") (pin "2") (pinfunction "K_2") (pintype "passive"))
    )
    (net (code "17") (name "/row6") (class "Default")
      (node (ref "D251") (pin "2") (pinfunction "K_2") (pintype "passive"))
      (node (ref "D257") (pin "2") (pinfunction "K_2") (pintype "passive"))
      (node (ref "D258") (pin "2") (pinfunction "K_2") (pintype "passive"))
      (node (ref "D260") (pin "2") (pinfunction "K_2") (pintype "passive"))
      (node (ref "D262") (pin "2") (pinfunction "K_2") (pintype "passive"))
      (node (ref "D264") (pin "2") (pinfunction "K_2") (pintype "passive"))
      (node (ref "D265") (pin "2") (pinfunction "K_2") (pintype "passive"))
      (node (ref "D266") (pin "2") (pinfunction "K_2") (pintype "passive"))
      (node (ref "D267") (pin "2") (pinfunction "K_2") (pintype "passive"))
    )
    (net (code "18") (name "Net-(D201-A)") (class "Default")
      (node (ref "D201") (pin "1") (pinfunction "A_1") (pintype "passive"))
      (node (ref "S201") (pin "1") (pinfunction "1_1") (pintype "passive"))
    )
    (net (code "19") (name "Net-(D202-A)") (class "Default")
      (node (ref "D202") (pin "1") (pinfunction "A_1") (pintype "passive"))
      (node (ref "S202") (pin "1") (pinfunction "1_1") (pintype "passive"))
    )
    (net (code "20") (name "Net-(D203-A)") (class "Default")
      (node (ref "D203") (pin "1") (pinfunction "A_1") (pintype "passive"))
      (node (ref "S203") (pin "1") (pinfunction "1_1") (pintype "passive"))
    )
    (net (code "21") (name "Net-(D204-A)") (class "Default")
      (node (ref "D204") (pin "1") (pinfunction "A_1") (pintype "passive"))
      (node (ref "S204") (pin "1") (pinfunction "1_1") (pintype "passive"))
    )
    (net (code "22") (name "Net-(D205-A)") (class "Default")
      (node (ref "D205") (pin "1") (pinfunction "A_1") (pintype "passive"))
      (node (ref "S205") (pin "1") (pinfunction "1_1") (pintype "passive"))
    )
    (net (code "23") (name "Net-(D206-A)") (class "Default")
      (node (ref "D206") (pin "1") (pinfunction "A_1") (pintype "passive"))
      (node (ref "S206") (pin "1") (pinfunction "1_1") (pintype "passive"))
    )
    (net (code "24") (name "Net-(D207-A)") (class "Default")
      (node (ref "D207") (pin "1") (pinfunction "A_1") (pintype "passive"))
      (node (ref "S207") (pin "1") (pinfunction "1_1") (pintype "passive"))
    )
    (net (code "25") (name "Net-(D208-A)") (class "Default")
      (node (ref "D208") (pin "1") (pinfunction "A_1") (pintype "passive"))
      (node (ref "S208") (pin "1") (pinfunction "1_1") (pintype "passive"))
    )
    (net (code "26") (name "Net-(D209-A)") (class "Default")
      (node (ref "D209") (pin "1") (pinfunction "A_1") (pintype "passive"))
      (node (ref "S209") (pin "1") (pinfunction "1_1") (pintype "passive"))
    )
    (net (code "27") (name "Net-(D210-A)") (class "Default")
      (node (ref "D210") (pin "1") (pinfunction "A_1") (pintype "passive"))
      (node (ref "S210") (pin "1") (pinfunction "1_1") (pintype "passive"))
    )
    (net (code "28") (name "Net-(D211-A)") (class "Default")
      (node (ref "D211") (pin "1") (pinfunction "A_1") (pintype "passive"))
      (node (ref "S211") (pin "1") (pinfunction "1_1") (pintype "passive"))
    )
    (net (code "29") (name "Net-(D212-A)") (class "Default")
      (node (ref "D212") (pin "1") (pinfunction "A_1") (pintype "passive"))
      (node (ref "S212") (pin "1") (pinfunction "1_1") (pintype "passive"))
    )
    (net (code "30") (name "Net-(D213-A)") (class "Default")
      (node (ref "D213") (pin "1") (pinfunction "A_1") (pintype "passive"))
      (node (ref "S213") (pin "1") (pinfunction "1_1") (pintype "passive"))
    )
    (net (code "31") (name "Net-(D214-A)") (class "Default")
      (node (ref "D214") (pin "1") (pinfunction "A_1") (pintype "passive"))
      (node (ref "S214") (pin "1") (pinfunction "1_1") (pintype "passive"))
    )
    (net (code "32") (name "Net-(D215-A)") (class "Default")
      (node (ref "D215") (pin "1") (pinfunction "A_1") (pintype "passive"))
      (node (ref "S215") (pin "1") (pinfunction "1_1") (pintype "passive"))
    )
    (net (code "33") (name "Net-(D216-A)") (class "Default")
      (node (ref "D216") (pin "1") (pinfunction "A_1") (pintype "passive"))
      (node (ref "S216") (pin "1") (pinfunction "1_1") (pintype "passive"))
    )
    (net (code "34") (name "Net-(D217-A)") (class "Default")
      (node (ref "D217") (pin "1") (pinfunction "A_1") (pintype "passive"))
      (node (ref "S217") (pin "1") (pinfunction "1_1") (pintype "passive"))
    )
    (net (code "35") (name "Net-(D218-A)") (class "Default")
      (node (ref "D218") (pin "1") (pinfunction "A_1") (pintype "passive"))
      (node (ref "S218") (pin "1") (pinfunction "1_1") (pintype "passive"))
    )
    (net (code "36") (name "Net-(D219-A)") (class "Default")
      (node (ref "D219") (pin "1") (pinfunction "A_1") (pintype "passive"))
      (node (ref "S219") (pin "1") (pinfunction "1_1") (pintype "passive"))
    )
    (net (code "37") (name "Net-(D220-A)") (class "Default")
      (node (ref "D220") (pin "1") (pinfunction "A_1") (pintype "passive"))
      (node (ref "S220") (pin "1") (pinfunction "1_1") (pintype "passive"))
    )
    (net (code "38") (name "Net-(D221-A)") (class "Default")
      (node (ref "D221") (pin "1") (pinfunction "A_1") (pintype "passive"))
      (node (ref "S221") (pin "1") (pinfunction "1_1") (pintype "passive"))
    )
    (net (code "39") (name "Net-(D222-A)") (class "Default")
      (node (ref "D222") (pin "1") (pinfunction "A_1") (pintype "passive"))
      (node (ref "S222") (pin "1") (pinfunction "1_1") (pintype "passive"))
    )
    (net (code "40") (name "Net-(D223-A)") (class "Default")
      (node (ref "D223") (pin "1") (pinfunction "A_1") (pintype "passive"))
      (node (ref "S223") (pin "1") (pinfunction "1_1") (pintype "passive"))
    )
    (net (code "41") (name "Net-(D224-A)") (class "Default")
      (node (ref "D224") (pin "1") (pinfunction "A_1") (pintype "passive"))
      (node (ref "S224") (pin "1") (pinfunction "1_1") (pintype "passive"))
    )
    (net (code "42") (name "Net-(D225-A)") (class "Default")
      (node (ref "D225") (pin "1") (pinfunction "A_1") (pintype "passive"))
      (node (ref "S225") (pin "1") (pinfunction "1_1") (pintype "passive"))
    )
    (net (code "43") (name "Net-(D226-A)") (class "Default")
      (node (ref "D226") (pin "1") (pinfunction "A_1") (pintype "passive"))
      (node (ref "S226") (pin "1") (pinfunction "1_1") (pintype "passive"))
    )
    (net (code "44") (name "Net-(D227-A)") (class "Default")
      (node (ref "D227") (pin "1") (pinfunction "A_1") (pintype "passive"))
      (node (ref "S227") (pin "1") (pinfunction "1_1") (pintype "passive"))
    )
    (net (code "45") (name "Net-(D228-A)") (class "Default")
      (node (ref "D228") (pin "1") (pinfunction "A_1") (pintype "passive"))
      (node (ref "S228") (pin "1") (pinfunction "1_1") (pintype "passive"))
      (node (ref "S228_2") (pin "1") (pinfunction "1_1") (pintype "passive"))
    )
    (net (code "46") (name "Net-(D229-A)") (class "Default")
      (node (ref "D229") (pin "1") (pinfunction "A_1") (pintype "passive"))
      (node (ref "S229") (pin "1") (pinfunction "1_1") (pintype "passive"))
    )
    (net (code "47") (name "Net-(D230-A)") (class "Default")
      (node (ref "D230") (pin "1") (pinfunction "A_1") (pintype "passive"))
      (node (ref "S230") (pin "1") (pinfunction "1_1") (pintype "passive"))
    )
    (net (code "48") (name "Net-(D231-A)") (class "Default")
      (node (ref "D231") (pin "1") (pinfunction "A_1") (pintype "passive"))
      (node (ref "S231") (pin "1") (pinfunction "1_1") (pintype "passive"))
    )
    (net (code "49") (name "Net-(D232-A)") (class "Default")
      (node (ref "D232") (pin "1") (pinfunction "A_1") (pintype "passive"))
      (node (ref "S232") (pin "1") (pinfunction "1_1") (pintype "passive"))
    )
    (net (code "50") (name "Net-(D233-A)") (class "Default")
      (node (ref "D233") (pin "1") (pinfunction "A_1") (pintype "passive"))
      (node (ref "S233") (pin "1") (pinfunction "1_1") (pintype "passive"))
    )
    (net (code "51") (name "Net-(D234-A)") (class "Default")
      (node (ref "D234") (pin "1") (pinfunction "A_1") (pintype "passive"))
      (node (ref "S234") (pin "1") (pinfunction "1_1") (pintype "passive"))
    )
    (net (code "52") (name "Net-(D235-A)") (class "Default")
      (node (ref "D235") (pin "1") (pinfunction "A_1") (pintype "passive"))
      (node (ref "S235") (pin "1") (pinfunction "1_1") (pintype "passive"))
    )
    (net (code "53") (name "Net-(D236-A)") (class "Default")
      (node (ref "D236") (pin "1") (pinfunction "A_1") (pintype "passive"))
      (node (ref "S236") (pin "1") (pinfunction "1_1") (pintype "passive"))
    )
    (net (code "54") (name "Net-(D237-A)") (class "Default")
      (node (ref "D237") (pin "1") (pinfunction "A_1") (pintype "passive"))
      (node (ref "S237") (pin "1") (pinfunction "1_1") (pintype "passive"))
    )
    (net (code "55") (name "Net-(D238-A)") (class "Default")
      (node (ref "D238") (pin "1") (pinfunction "A_1") (pintype "passive"))
      (node (ref "S238") (pin "1") (pinfunction "1_1") (pintype "passive"))
    )
    (net (code "56") (name "Net-(D239-A)") (class "Default")
      (node (ref "D239") (pin "1") (pinfunction "A_1") (pintype "passive"))
      (node (ref "S239") (pin "1") (pinfunction "1_1") (pintype "passive"))
    )
    (net (code "57") (name "Net-(D240-A)") (class "Default")
      (node (ref "D240") (pin "1") (pinfunction "A_1") (pintype "passive"))
      (node (ref "S240") (pin "1") (pinfunction "1_1") (pintype "passive"))
    )
    (net (code "58") (name "Net-(D242-A)") (class "Default")
      (node (ref "D242") (pin "1") (pinfunction "A_1") (pintype "passive"))
      (node (ref "S242") (pin "1") (pinfunction "1_1") (pintype "passive"))
    )
    (net (code "59") (name "Net-(D243-A)") (class "Default")
      (node (ref "D243") (pin "1") (pinfunction "A_1") (pintype "passive"))
      (node (ref "S243") (pin "1") (pinfunction "1_1") (pintype "passive"))
    )
    (net (code "60") (name "Net-(D244-A)") (class "Default")
      (node (ref "D244") (pin "1") (pinfunction "A_1") (pintype "passive"))
      (node (ref "S244") (pin "1") (pinfunction "1_1") (pintype "passive"))
    )
    (net (code "61") (name "Net-(D245-A)") (class "Default")
      (node (ref "D245") (pin "1") (pinfunction "A_1") (pintype "passive"))
      (node (ref "S245") (pin "1") (pinfunction "1_1") (pintype "passive"))
    )
    (net (code "62") (name "Net-(D246-A)") (class "Default")
      (node (ref "D246") (pin "1") (pinfunction "A_1") (pintype "passive"))
      (node (ref "S246") (pin "1") (pinfunction "1_1") (pintype "passive"))
    )
    (net (code "63") (name "Net-(D247-A)") (class "Default")
      (node (ref "D247") (pin "1") (pinfunction "A_1") (pintype "passive"))
      (node (ref "S247") (pin "1") (pinfunction "1_1") (pintype "passive"))
    )
    (net (code "64") (name "Net-(D248-A)") (class "Default")
      (node (ref "D248") (pin "1") (pinfunction "A_1") (pintype "passive"))
      (node (ref "S248") (pin "1") (pinfunction "1_1") (pintype "passive"))
    )
    (net (code "65") (name "Net-(D249-A)") (class "Default")
      (node (ref "D249") (pin "1") (pinfunction "A_1") (pintype "passive"))
      (node (ref "S249") (pin "1") (pinfunction "1_1") (pintype "passive"))
    )
    (net (code "66") (name "Net-(D250-A)") (class "Default")
      (node (ref "D250") (pin "1") (pinfunction "A_1") (pintype "passive"))
      (node (ref "S250") (pin "1") (pinfunction "1_1") (pintype "passive"))
    )
    (net (code "67") (name "Net-(D251-A)") (class "Default")
      (node (ref "D251") (pin "1") (pinfunction "A_1") (pintype "passive"))
      (node (ref "S251") (pin "1") (pinfunction "1_1") (pintype "passive"))
    )
    (net (code "68") (name "Net-(D252-A)") (class "Default")
      (node (ref "D252") (pin "1") (pinfunction "A_1") (pintype "passive"))
      (node (ref "S252") (pin "1") (pinfunction "1_1") (pintype "passive"))
    )
    (net (code "69") (name "Net-(D253-A)") (class "Default")
      (node (ref "D253") (pin "1") (pinfunction "A_1") (pintype "passive"))
      (node (ref "S253") (pin "1") (pinfunction "1_1") (pintype "passive"))
    )
    (net (code "70") (name "Net-(D254-A)") (class "Default")
      (node (ref "D254") (pin "1") (pinfunction "A_1") (pintype "passive"))
      (node (ref "S254") (pin "1") (pinfunction "1_1") (pintype "passive"))
    )
    (net (code "71") (name "Net-(D256-A)") (class "Default")
      (node (ref "D256") (pin "1") (pinfunction "A_1") (pintype "passive"))
      (node (ref "S256") (pin "1") (pinfunction "1_1") (pintype "passive"))
    )
    (net (code "72") (name "Net-(D257-A)") (class "Default")
      (node (ref "D257") (pin "1") (pinfunction "A_1") (pintype "passive"))
      (node (ref "S257") (pin "1") (pinfunction "1_1") (pintype "passive"))
    )
    (net (code "73") (name "Net-(D258-A)") (class "Default")
      (node (ref "D258") (pin "1") (pinfunction "A_1") (pintype "passive"))
      (node (ref "S258") (pin "2") (pinfunction "2_2") (pintype "passive"))
    )
    (net (code "74") (name "Net-(D259-A)") (class "Default")
      (node (ref "D259") (pin "1") (pinfunction "A_1") (pintype "passive"))
      (node (ref "S259") (pin "1") (pinfunction "1_1") (pintype "passive"))
    )
    (net (code "75") (name "Net-(D260-A)") (class "Default")
      (node (ref "D260") (pin "1") (pinfunction "A_1") (pintype "passive"))
      (node (ref "S260") (pin "1") (pinfunction "1_1") (pintype "passive"))
    )
    (net (code "76") (name "Net-(D262-A)") (class "Default")
      (node (ref "D262") (pin "1") (pinfunction "A_1") (pintype "passive"))
      (node (ref "S262") (pin "1") (pinfunction "1_1") (pintype "passive"))
    )
    (net (code "77") (name "Net-(D264-A)") (class "Default")
      (node (ref "D264") (pin "1") (pinfunction "A_1") (pintype "passive"))
      (node (ref "S264") (pin "1") (pinfunction "1_1") (pintype "passive"))
    )
    (net (code "78") (name "Net-(D265-A)") (class "Default")
      (node (ref "D265") (pin "1") (pinfunction "A_1") (pintype "passive"))
      (node (ref "S265") (pin "2") (pinfunction "2_2") (pintype "passive"))
    )
    (net (code "79") (name "Net-(D266-A)") (class "Default")
      (node (ref "D266") (pin "1") (pinfunction "A_1") (pintype "passive"))
      (node (ref "S266") (pin "2") (pinfunction "2_2") (pintype "passive"))
    )
    (net (code "80") (name "Net-(D267-A)") (class "Default")
      (node (ref "D267") (pin "1") (pinfunction "A_1") (pintype "passive"))
      (node (ref "S267") (pin "1") (pinfunction "1_1") (pintype "passive"))
    )
    (net (code "81") (name "Net-(D269-A)") (class "Default")
      (node (ref "D269") (pin "1") (pinfunction "A_1") (pintype "passive"))
      (node (ref "S269") (pin "1") (pinfunction "1_1") (pintype "passive"))
    )
  )
)
